# Signal_Processing.net
KiCad netlist of a schematic drawn in Altium Designer
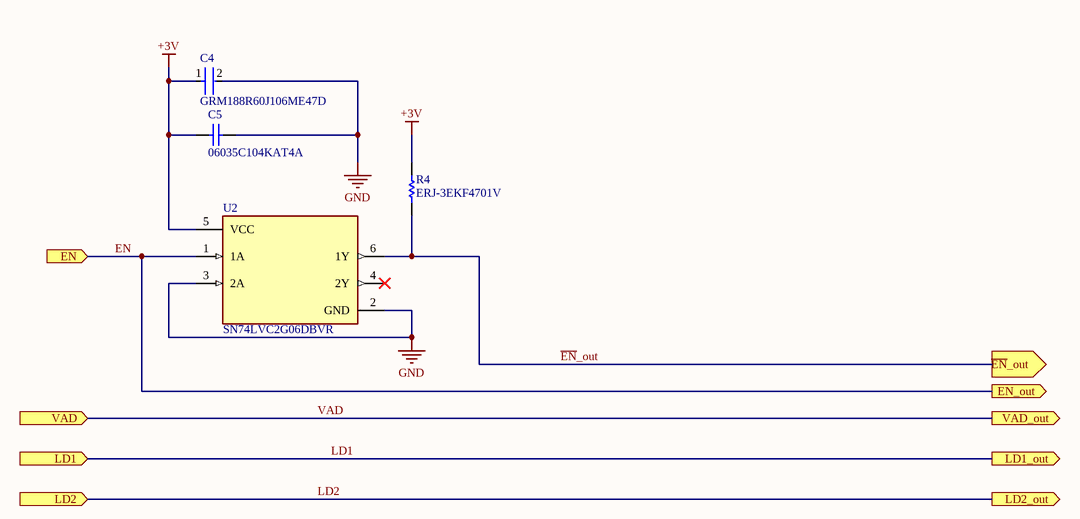
[diagram p0: Signal Processing.SchDoc]

(export (version "E")
  (design (tool "Eeschema 10.0.6"))
  (components
    (comp (ref "C4")
      (value "GRM188R60J106ME47D")
      (footprint "FP-GRM188-0_1-e0_2_0_55-IPC_A")
      (description "Chip Multilayer Ceramic Capacitors for General Purpose, 0603, 10uF, X5R, 15%, 20%, 6.3V")
      (fields (field (name "VOLTAGE") "6.3V") (field (name "TOLERANCE") "20%"))
      (libsource (lib "Altium Content Vault") (part "02cd4be3c70576c341d710602a673aa"))
    )
    (comp (ref "C5")
      (value "06035C104KAT4A")
      (footprint "CAPC1608X90X35LL15T15")
      (fields (field (name "MANUFACTURER") "AVX Interconnect / Elco"))
      (libsource (lib "Altium Content Vault") (part "CAP"))
    )
    (comp (ref "R4")
      (value "ERJ-3EKF4701V")
      (footprint "RESC1608X55X30NL15T15")
      (fields (field (name "TOLERANCE") "5%"))
      (libsource (lib "Altium Content Vault") (part "RES-2"))
    )
    (comp (ref "U2")
      (value "SN74LVC2G06DBVR")
      (footprint "FP-DBV0006A-IPC_A")
      (description "IC INVERTER 2CH 2-INP SOT23-6")
      (libsource (lib "Altium Content Vault") (part "8436e229ae875cd86fe2e23916178cc"))
    )
  )
  (nets
    (net (code "1") (name "+3V") (class "Default")
      (node (ref "C4") (pin "1") (pinfunction "1_1") (pintype "passive"))
      (node (ref "C5") (pin "2") (pinfunction "2_2") (pintype "passive"))
      (node (ref "R4") (pin "2") (pinfunction "2_2") (pintype "passive"))
      (node (ref "U2") (pin "5") (pinfunction "VCC_5") (pintype "power_in"))
    )
    (net (code "2") (name "/EN") (class "Default")
      (node (ref "U2") (pin "1") (pinfunction "1A_1") (pintype "input"))
    )
    (net (code "6") (name "/~{EN}_out") (class "Default")
      (node (ref "R4") (pin "1") (pinfunction "1_1") (pintype "passive"))
      (node (ref "U2") (pin "6") (pinfunction "1Y_6") (pintype "output"))
    )
    (net (code "7") (name "GND") (class "Default")
      (node (ref "C4") (pin "2") (pinfunction "2_2") (pintype "passive"))
      (node (ref "C5") (pin "1") (pinfunction "1_1") (pintype "passive"))
      (node (ref "U2") (pin "2") (pinfunction "GND_2") (pintype "power_in"))
      (node (ref "U2") (pin "3") (pinfunction "2A_3") (pintype "input"))
    )
    (net (code "8") (name "unconnected-(U2-2Y-Pad4)") (class "Default")
      (node (ref "U2") (pin "4") (pinfunction "2Y_4") (pintype "output+no_connect"))
    )
  )
)
